# ow_switch2.net
KiCad netlist of a schematic drawn in EAGLE
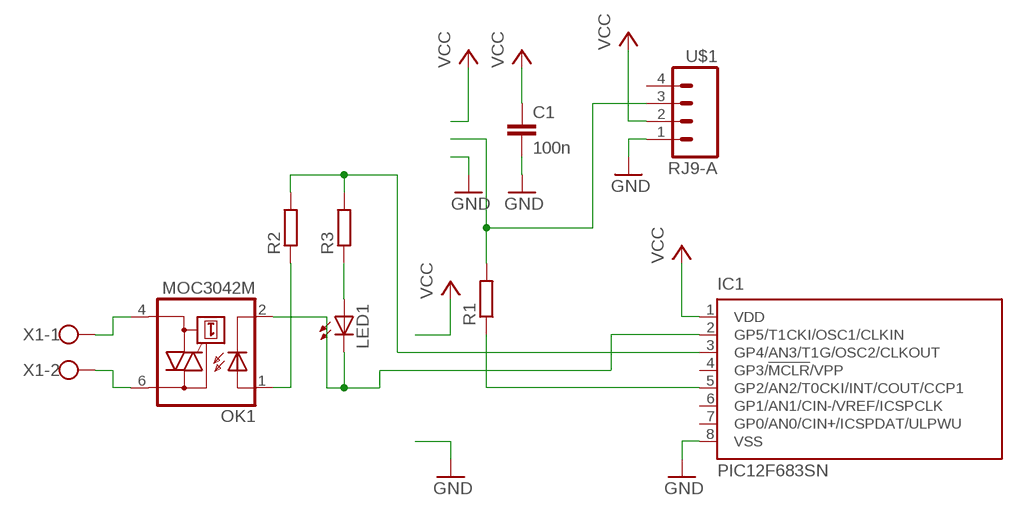
[diagram p0: schematic, sheet 1]

(export (version "E")
  (design (tool "Eeschema 10.0.6"))
  (components
    (comp (ref "C1")
      (value "100n")
      (footprint "eagle-import:C1206")
      (libsource (lib "eagle-import") (part "C-EUC1206"))
    )
    (comp (ref "IC1")
      (value "PIC12F683SN")
      (footprint "eagle-import:SO-08")
      (fields (field (name "MF") "MICROCHIP") (field (name "MPN") "PIC12F683-I/SN"))
      (libsource (lib "eagle-import") (part "PIC12F683SN"))
    )
    (comp (ref "LED1")
      (value "LEDSMT1206")
      (footprint "eagle-import:1206")
      (libsource (lib "eagle-import") (part "LEDSMT1206"))
    )
    (comp (ref "OK1")
      (value "MOC3042M")
      (footprint "eagle-import:DIL06")
      (fields (field (name "MF") "FAIRCHILD SEMICONDUCTOR") (field (name "MPN") "MOC3042-M"))
      (libsource (lib "eagle-import") (part "MOC3042M"))
    )
    (comp (ref "R1")
      (value "R-EU_R1206")
      (footprint "eagle-import:R1206")
      (libsource (lib "eagle-import") (part "R-EU_R1206"))
    )
    (comp (ref "R2")
      (value "R-EU_R1206")
      (footprint "eagle-import:R1206")
      (libsource (lib "eagle-import") (part "R-EU_R1206"))
    )
    (comp (ref "R3")
      (value "R-EU_R1206")
      (footprint "eagle-import:R1206")
      (libsource (lib "eagle-import") (part "R-EU_R1206"))
    )
    (comp (ref "U$1")
      (value "RJ9-A")
      (footprint "eagle-import:RJ9-A")
      (libsource (lib "eagle-import") (part "RJ9-A"))
    )
    (comp (ref "X1")
      (value "W237-102")
      (footprint "eagle-import:W237-102")
      (fields (field (name "MPN") "237-102"))
      (libsource (lib "eagle-import") (part "W237-102"))
    )
  )
  (nets
    (net (code "1") (name "GND") (class "Default")
      (node (ref "C1") (pin "2") (pinfunction "2_2") (pintype "passive"))
      (node (ref "IC1") (pin "8") (pinfunction "VSS_8") (pintype "power_in"))
      (node (ref "U$1") (pin "1") (pinfunction "1_1") (pintype "passive"))
    )
    (net (code "2") (name "Net-(IC1-GP2{slash}AN2{slash}T0CKI{slash}INT{slash}COUT{slash}CCP1)") (class "Default")
      (node (ref "IC1") (pin "5") (pinfunction "GP2/AN2/T0CKI/INT/COUT/CCP1_5") (pintype "bidirectional"))
      (node (ref "R1") (pin "1") (pinfunction "1_1") (pintype "passive"))
    )
    (net (code "3") (name "Net-(IC1-GP4{slash}AN3{slash}T1G{slash}OSC2{slash}CLKOUT)") (class "Default")
      (node (ref "IC1") (pin "3") (pinfunction "GP4/AN3/T1G/OSC2/CLKOUT_3") (pintype "bidirectional"))
      (node (ref "R2") (pin "2") (pinfunction "2_2") (pintype "passive"))
      (node (ref "R3") (pin "2") (pinfunction "2_2") (pintype "passive"))
    )
    (net (code "4") (name "Net-(IC1-GP5{slash}T1CKI{slash}OSC1{slash}CLKIN)") (class "Default")
      (node (ref "IC1") (pin "2") (pinfunction "GP5/T1CKI/OSC1/CLKIN_2") (pintype "bidirectional"))
      (node (ref "LED1") (pin "C") (pinfunction "C_C") (pintype "passive"))
      (node (ref "OK1") (pin "2") (pinfunction "C_2") (pintype "passive"))
    )
    (net (code "5") (name "Net-(LED1-PadA)") (class "Default")
      (node (ref "LED1") (pin "A") (pinfunction "A_A") (pintype "passive"))
      (node (ref "R3") (pin "1") (pinfunction "1_1") (pintype "passive"))
    )
    (net (code "6") (name "Net-(OK1-A)") (class "Default")
      (node (ref "OK1") (pin "1") (pinfunction "A_1") (pintype "passive"))
      (node (ref "R2") (pin "1") (pinfunction "1_1") (pintype "passive"))
    )
    (net (code "7") (name "Net-(OK1-A1)") (class "Default")
      (node (ref "OK1") (pin "4") (pinfunction "A1_4") (pintype "passive"))
      (node (ref "X1") (pin "1") (pinfunction "KL_1") (pintype "passive"))
    )
    (net (code "8") (name "Net-(OK1-A2)") (class "Default")
      (node (ref "OK1") (pin "6") (pinfunction "A2_6") (pintype "passive"))
      (node (ref "X1") (pin "2") (pinfunction "KL_2") (pintype "passive"))
    )
    (net (code "9") (name "Net-(R1-Pad2)") (class "Default")
      (node (ref "R1") (pin "2") (pinfunction "2_2") (pintype "passive"))
      (node (ref "U$1") (pin "3") (pinfunction "3_3") (pintype "passive"))
    )
    (net (code "10") (name "VCC") (class "Default")
      (node (ref "C1") (pin "1") (pinfunction "1_1") (pintype "passive"))
      (node (ref "IC1") (pin "1") (pinfunction "VDD_1") (pintype "power_in"))
      (node (ref "U$1") (pin "2") (pinfunction "2_2") (pintype "passive"))
    )
    (net (code "11") (name "unconnected-(IC1-GP0{slash}AN0{slash}CIN+{slash}ICSPDAT{slash}ULPWU-Pad7)") (class "Default")
      (node (ref "IC1") (pin "7") (pinfunction "GP0/AN0/CIN+/ICSPDAT/ULPWU_7") (pintype "bidirectional"))
    )
    (net (code "12") (name "unconnected-(IC1-GP1{slash}AN1{slash}CIN-{slash}VREF{slash}ICSPCLK-Pad6)") (class "Default")
      (node (ref "IC1") (pin "6") (pinfunction "GP1/AN1/CIN-/VREF/ICSPCLK_6") (pintype "bidirectional"))
    )
    (net (code "13") (name "unconnected-(IC1-GP3{slash}~{MCLR}{slash}VPP-Pad4)") (class "Default")
      (node (ref "IC1") (pin "4") (pinfunction "GP3/~{MCLR}/VPP_4") (pintype "bidirectional"))
    )
    (net (code "14") (name "unconnected-(U$1-Pad4)") (class "Default")
      (node (ref "U$1") (pin "4") (pinfunction "4_4") (pintype "passive"))
    )
  )
)
